# power.net
KiCad netlist of a schematic drawn in EAGLE
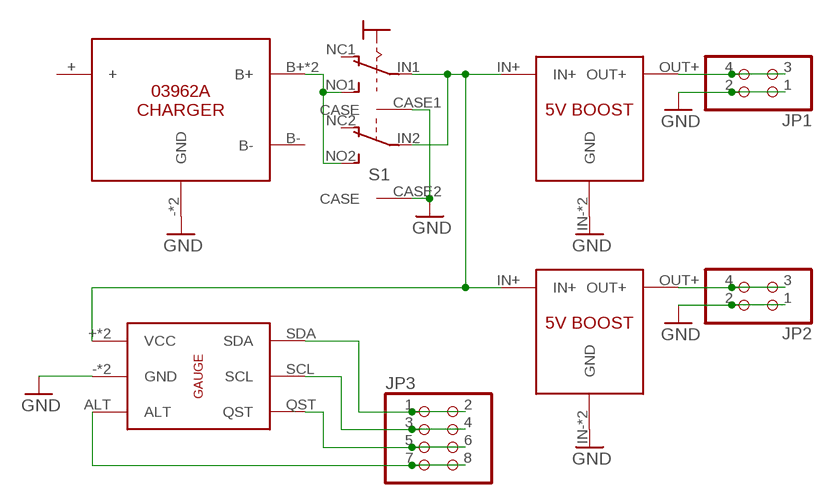
[diagram p0: schematic, sheet 1]

(export (version "E")
  (design (tool "Eeschema 10.0.6"))
  (components
    (comp (ref "JP1")
      (value "PINHD-2X2/90")
      (footprint "eagle-import:2X02_90")
      (libsource (lib "eagle-import") (part "PINHD-2X2/90"))
    )
    (comp (ref "JP2")
      (value "PINHD-2X2/90")
      (footprint "eagle-import:2X02_90")
      (libsource (lib "eagle-import") (part "PINHD-2X2/90"))
    )
    (comp (ref "JP3")
      (value "PINHD-2X4/90")
      (footprint "eagle-import:2X04_90")
      (libsource (lib "eagle-import") (part "PINHD-2X4/90"))
    )
    (comp (ref "S1")
      (value "PUSHSWITCH")
      (footprint "eagle-import:PUSHSWITCH")
      (libsource (lib "eagle-import") (part "PUSHSWITCH"))
    )
    (comp (ref "U$1")
      (value "03962A")
      (footprint "eagle-import:03962A")
      (libsource (lib "eagle-import") (part "03962A"))
    )
    (comp (ref "U$2")
      (value "5VBOOST")
      (footprint "eagle-import:5VBOOST")
      (libsource (lib "eagle-import") (part "5VBOOST"))
    )
    (comp (ref "U$3")
      (value "5VBOOST")
      (footprint "eagle-import:5VBOOST")
      (libsource (lib "eagle-import") (part "5VBOOST"))
    )
    (comp (ref "U$4")
      (value "GAUGE")
      (footprint "eagle-import:GAUGE")
      (libsource (lib "eagle-import") (part "GAUGE"))
    )
  )
  (nets
    (net (code "1") (name "GND") (class "Default")
      (node (ref "JP1") (pin "1") (pinfunction "1_1") (pintype "passive"))
      (node (ref "JP1") (pin "2") (pinfunction "2_2") (pintype "passive"))
      (node (ref "JP2") (pin "1") (pinfunction "1_1") (pintype "passive"))
      (node (ref "JP2") (pin "2") (pinfunction "2_2") (pintype "passive"))
      (node (ref "S1") (pin "CASE1") (pinfunction "CASE_CASE1") (pintype "passive"))
      (node (ref "S1") (pin "CASE2") (pinfunction "CASE_CASE2") (pintype "passive"))
      (node (ref "U$1") (pin "-") (pinfunction "GND_-") (pintype "bidirectional"))
      (node (ref "U$1") (pin "OUT-") (pinfunction "GND_OUT-") (pintype "bidirectional"))
      (node (ref "U$2") (pin "IN-") (pinfunction "GND_IN-") (pintype "bidirectional"))
      (node (ref "U$2") (pin "OUT-") (pinfunction "GND_OUT-") (pintype "bidirectional"))
      (node (ref "U$3") (pin "IN-") (pinfunction "GND_IN-") (pintype "bidirectional"))
      (node (ref "U$3") (pin "OUT-") (pinfunction "GND_OUT-") (pintype "bidirectional"))
      (node (ref "U$4") (pin "-") (pinfunction "GND_-") (pintype "bidirectional"))
      (node (ref "U$4") (pin "GND") (pinfunction "GND_GND") (pintype "bidirectional"))
    )
    (net (code "2") (name "Net-(JP1-Pad3)") (class "Default")
      (node (ref "JP1") (pin "3") (pinfunction "3_3") (pintype "passive"))
      (node (ref "JP1") (pin "4") (pinfunction "4_4") (pintype "passive"))
      (node (ref "U$2") (pin "OUT+") (pinfunction "OUT+_OUT+") (pintype "bidirectional"))
    )
    (net (code "3") (name "Net-(JP2-Pad3)") (class "Default")
      (node (ref "JP2") (pin "3") (pinfunction "3_3") (pintype "passive"))
      (node (ref "JP2") (pin "4") (pinfunction "4_4") (pintype "passive"))
      (node (ref "U$3") (pin "OUT+") (pinfunction "OUT+_OUT+") (pintype "bidirectional"))
    )
    (net (code "4") (name "Net-(JP3-Pad1)") (class "Default")
      (node (ref "JP3") (pin "1") (pinfunction "1_1") (pintype "passive"))
      (node (ref "JP3") (pin "2") (pinfunction "2_2") (pintype "passive"))
      (node (ref "U$4") (pin "SDA") (pinfunction "SDA_SDA") (pintype "bidirectional"))
    )
    (net (code "5") (name "Net-(JP3-Pad3)") (class "Default")
      (node (ref "JP3") (pin "3") (pinfunction "3_3") (pintype "passive"))
      (node (ref "JP3") (pin "4") (pinfunction "4_4") (pintype "passive"))
      (node (ref "U$4") (pin "SCL") (pinfunction "SCL_SCL") (pintype "bidirectional"))
    )
    (net (code "6") (name "Net-(JP3-Pad5)") (class "Default")
      (node (ref "JP3") (pin "5") (pinfunction "5_5") (pintype "passive"))
      (node (ref "JP3") (pin "6") (pinfunction "6_6") (pintype "passive"))
      (node (ref "U$4") (pin "QST") (pinfunction "QST_QST") (pintype "bidirectional"))
    )
    (net (code "7") (name "Net-(JP3-Pad7)") (class "Default")
      (node (ref "JP3") (pin "7") (pinfunction "7_7") (pintype "passive"))
      (node (ref "JP3") (pin "8") (pinfunction "8_8") (pintype "passive"))
      (node (ref "U$4") (pin "ALT") (pinfunction "ALT_ALT") (pintype "bidirectional"))
    )
    (net (code "8") (name "Net-(S1A-IN)") (class "Default")
      (node (ref "S1") (pin "IN1") (pinfunction "IN_IN1") (pintype "passive"))
      (node (ref "S1") (pin "IN2") (pinfunction "IN_IN2") (pintype "passive"))
      (node (ref "U$2") (pin "IN+") (pinfunction "IN+_IN+") (pintype "bidirectional"))
      (node (ref "U$3") (pin "IN+") (pinfunction "IN+_IN+") (pintype "bidirectional"))
      (node (ref "U$4") (pin "+") (pinfunction "VCC_+") (pintype "bidirectional"))
      (node (ref "U$4") (pin "VCC") (pinfunction "VCC_VCC") (pintype "bidirectional"))
    )
    (net (code "9") (name "Net-(S1A-NO)") (class "Default")
      (node (ref "S1") (pin "NO1") (pinfunction "NO_NO1") (pintype "passive"))
      (node (ref "S1") (pin "NO2") (pinfunction "NO_NO2") (pintype "passive"))
      (node (ref "U$1") (pin "B+") (pinfunction "B+_B+") (pintype "bidirectional"))
      (node (ref "U$1") (pin "OUT+") (pinfunction "B+_OUT+") (pintype "bidirectional"))
    )
    (net (code "10") (name "unconnected-(S1A-NC-PadNC1)") (class "Default")
      (node (ref "S1") (pin "NC1") (pinfunction "NC_NC1") (pintype "passive"))
    )
    (net (code "11") (name "unconnected-(S1B-NC-PadNC2)") (class "Default")
      (node (ref "S1") (pin "NC2") (pinfunction "NC_NC2") (pintype "passive"))
    )
    (net (code "12") (name "unconnected-(U$1-Pad+)") (class "Default")
      (node (ref "U$1") (pin "+") (pinfunction "+_+") (pintype "bidirectional"))
    )
    (net (code "13") (name "unconnected-(U$1-PadB-)") (class "Default")
      (node (ref "U$1") (pin "B-") (pinfunction "B-_B-") (pintype "bidirectional"))
    )
  )
)
